# Chua_circuit.net
KiCad netlist of a schematic drawn in Altium Designer
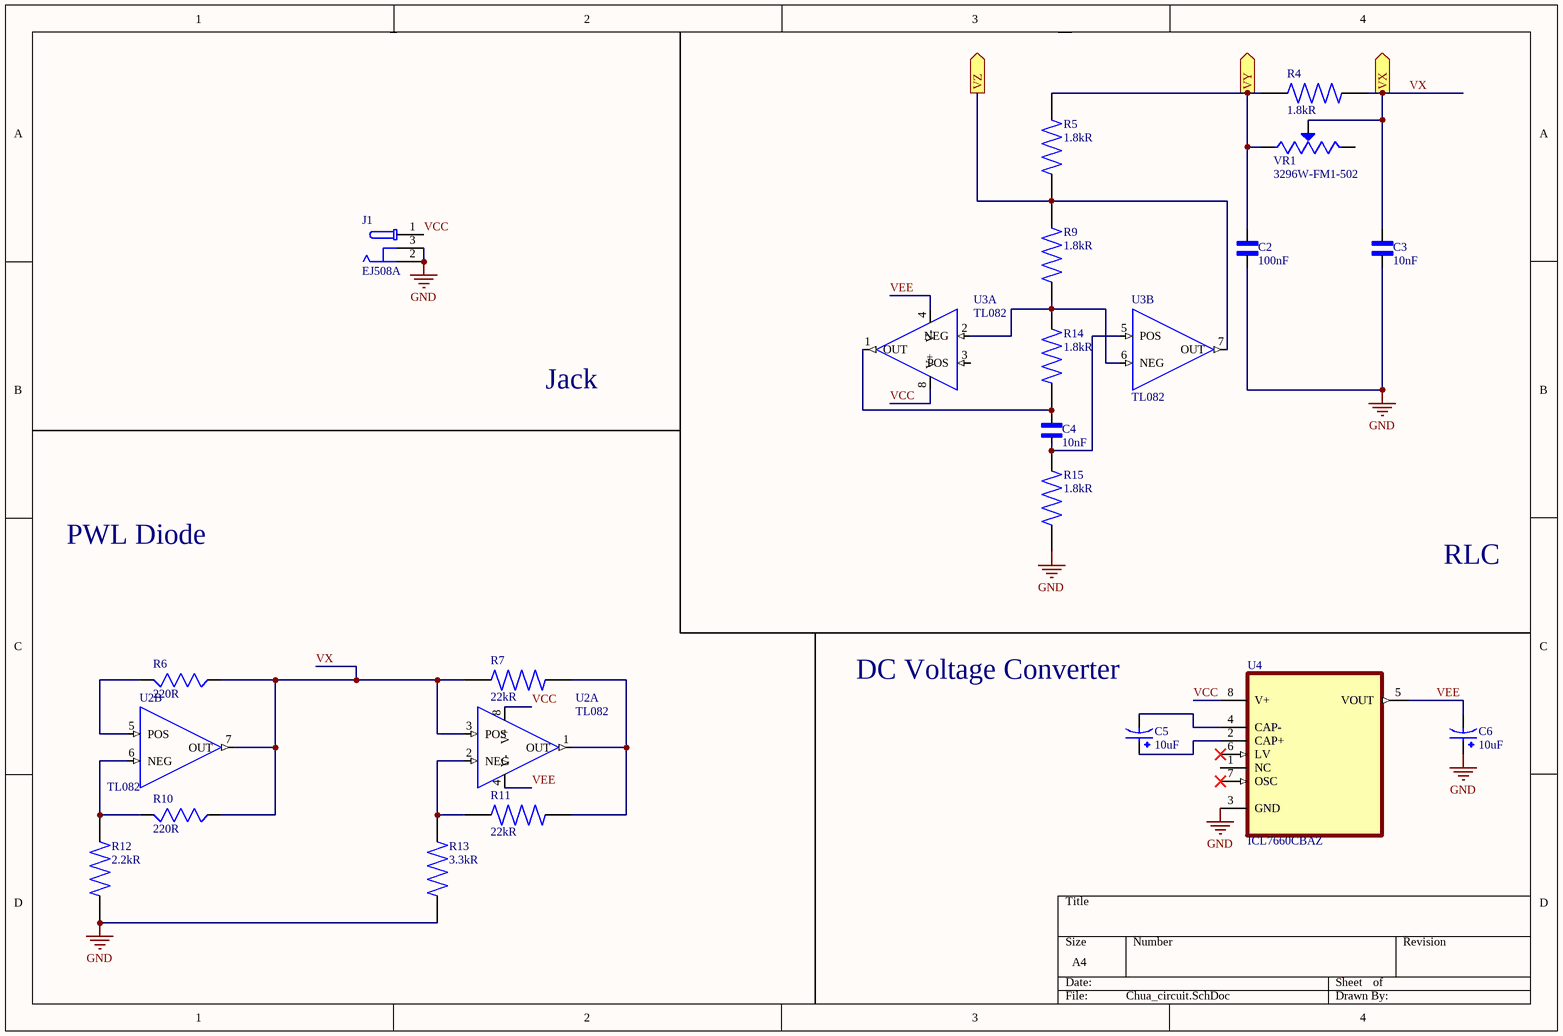
[diagram p0: Chua_circuit.SchDoc]

(export (version "E")
  (design (tool "Eeschema 10.0.6"))
  (components
    (comp (ref "C2")
      (value "100nF")
      (footprint "CAPC3216X100N")
      (description "Ceramic capacitor SMD 1206 100 nF 50 V 10 % Samsung Electro-Mechanics CL31B104KBCNNNC 4000 pc(s)")
      (fields (field (name "MF") "Samsung Electro-Mechanics") (field (name "MP") "CL31B104KBCNNNC"))
      (libsource (lib "CL31B104KBCNNNC") (part "CL31B104KBCNNNC"))
    )
    (comp (ref "C3")
      (value "10nF")
      (footprint "CAPC1608X90N")
      (description "0603 X7R ceramic capacitor,10nF 25V ¦ AVX 06033C103KAT2A")
      (fields (field (name "MF") "AVX") (field (name "MP") "06033C103KAT2A"))
      (libsource (lib "06033C103KAT2A") (part "06033C103KAT2A"))
    )
    (comp (ref "C4")
      (value "10nF")
      (footprint "CAPC1608X90N")
      (description "0603 X7R ceramic capacitor,10nF 25V ¦ AVX 06033C103KAT2A")
      (fields (field (name "MF") "AVX") (field (name "MP") "06033C103KAT2A"))
      (libsource (lib "06033C103KAT2A") (part "06033C103KAT2A"))
    )
    (comp (ref "C5")
      (value "10uF")
      (footprint "CAP_EEEFN1J100L")
      (description "CAP ALUM 10UF 20% 63V SMD")
      (fields (field (name "MF") "Panasonic") (field (name "MP") "EEEFN1J100L"))
      (libsource (lib "EEEFN1J100L") (part "EEEFN1J100L"))
    )
    (comp (ref "C6")
      (value "10uF")
      (footprint "CAP_EEEFN1J100L")
      (description "CAP ALUM 10UF 20% 63V SMD")
      (fields (field (name "MF") "Panasonic") (field (name "MP") "EEEFN1J100L"))
      (libsource (lib "EEEFN1J100L") (part "EEEFN1J100L"))
    )
    (comp (ref "J1")
      (value "EJ508A")
      (footprint "MPD_EJ508A")
      (description "Power Barrel Connector Jack 2.10mm ID _0.083_, 5.50mm OD _0.217_ Through Hole, Right Angle")
      (fields (field (name "MF") "MPD"))
      (libsource (lib "EJ508A") (part "EJ508A"))
    )
    (comp (ref "R4")
      (value "1.8kR")
      (footprint "RES_ERJU08F1801V")
      (fields (field (name "MP") "ERJU08F1801V"))
      (libsource (lib "ERJU08F1801V") (part "ERJU08F1801V"))
    )
    (comp (ref "R5")
      (value "1.8kR")
      (footprint "RES_ERJU08F1801V")
      (fields (field (name "MP") "ERJU08F1801V"))
      (libsource (lib "ERJU08F1801V") (part "ERJU08F1801V"))
    )
    (comp (ref "R6")
      (value "220R")
      (footprint "RESC2012X60N")
      (description "220 kOhms Â±1% 0.125W, 1/8W Chip Resistor 0805 (2012 Metric) - Thick Film")
      (fields (field (name "MP") "RC0805FR-10220KL") (field (name "MF") "Yageo"))
      (libsource (lib "RC0805FR-10220KL") (part "RC0805FR-10220KL"))
    )
    (comp (ref "R7")
      (value "22kR")
      (footprint "RES_ERA3AED223V")
      (fields (field (name "MP") "ERA3AED223V"))
      (libsource (lib "ERA3AED223V") (part "ERA3AED223V"))
    )
    (comp (ref "R9")
      (value "1.8kR")
      (footprint "RES_ERJU08F1801V")
      (fields (field (name "MP") "ERJU08F1801V"))
      (libsource (lib "ERJU08F1801V") (part "ERJU08F1801V"))
    )
    (comp (ref "R10")
      (value "220R")
      (footprint "RESC2012X60N")
      (description "220 kOhms Â±1% 0.125W, 1/8W Chip Resistor 0805 (2012 Metric) - Thick Film")
      (fields (field (name "MP") "RC0805FR-10220KL") (field (name "MF") "Yageo"))
      (libsource (lib "RC0805FR-10220KL") (part "RC0805FR-10220KL"))
    )
    (comp (ref "R11")
      (value "22kR")
      (footprint "RES_ERA3AED223V")
      (fields (field (name "MP") "ERA3AED223V"))
      (libsource (lib "ERA3AED223V") (part "ERA3AED223V"))
    )
    (comp (ref "R12")
      (value "2.2kR")
      (footprint "RESC1608X55N")
      (description "Res 0603 2k2 5% 100mW ¦ Bourns CR0603-JW-222ELF")
      (fields (field (name "MF") "Bourns") (field (name "MP") "CR0603-JW-222ELF"))
      (libsource (lib "CR0603-JW-222ELF") (part "CR0603-JW-222ELF"))
    )
    (comp (ref "R13")
      (value "3.3kR")
      (footprint "RESC1608X55N")
      (description "CR0603 SMD Thick Film Resistor,3K3 1% ¦ Bourns CR0603-FX-3301ELF")
      (fields (field (name "MF") "Bourns") (field (name "MP") "CR0603-FX-3301ELF"))
      (libsource (lib "CR0603-FX-3301ELF") (part "CR0603-FX-3301ELF"))
    )
    (comp (ref "R14")
      (value "1.8kR")
      (footprint "RES_ERJU08F1801V")
      (fields (field (name "MP") "ERJU08F1801V"))
      (libsource (lib "ERJU08F1801V") (part "ERJU08F1801V"))
    )
    (comp (ref "R15")
      (value "1.8kR")
      (footprint "RES_ERJU08F1801V")
      (fields (field (name "MP") "ERJU08F1801V"))
      (libsource (lib "ERJU08F1801V") (part "ERJU08F1801V"))
    )
    (comp (ref "U2")
      (value "TL082")
      (footprint "SOIC127P600X175-8N")
      (description "GENERAL PURPOSE J-FET DUAL OPERATIONAL AMPLIFIERS")
      (fields (field (name "MF") "STMicroelectronics"))
      (libsource (lib "TL082") (part "TL082"))
    )
    (comp (ref "U3")
      (value "TL082")
      (footprint "SOIC127P600X175-8N")
      (description "GENERAL PURPOSE J-FET DUAL OPERATIONAL AMPLIFIERS")
      (fields (field (name "MF") "STMicroelectronics"))
      (libsource (lib "TL082") (part "TL082"))
    )
    (comp (ref "U4")
      (value "ICL7660CBAZ")
      (footprint "SOIC127P600X175-8N")
      (fields (field (name "MF") "Renesas Electronics America Inc"))
      (libsource (lib "ICL7660CBAZ") (part "ICL7660CBAZ"))
    )
    (comp (ref "VR1")
      (value "3296W-FM1-502")
      (footprint "TRIM_3296W-FM1-502")
      (description "Trimmer Resistors - Through Hole")
      (fields (field (name "MF") "Bourns"))
      (libsource (lib "3296W-FM1-502") (part "3296W-FM1-502"))
    )
  )
  (nets
    (net (code "1") (name "/VCC") (class "Default")
      (node (ref "J1") (pin "1") (pinfunction "1_1") (pintype "passive"))
      (node (ref "U2") (pin "8") (pinfunction "V+_8") (pintype "power_in"))
      (node (ref "U3") (pin "8") (pinfunction "V+_8") (pintype "power_in"))
      (node (ref "U4") (pin "8") (pinfunction "V+_8") (pintype "power_in"))
    )
    (net (code "2") (name "/VEE") (class "Default")
      (node (ref "C6") (pin "2") (pinfunction "2_2") (pintype "passive"))
      (node (ref "U2") (pin "4") (pinfunction "V-_4") (pintype "power_in"))
      (node (ref "U3") (pin "4") (pinfunction "V-_4") (pintype "power_in"))
      (node (ref "U4") (pin "5") (pinfunction "VOUT_5") (pintype "output"))
    )
    (net (code "3") (name "/VX") (class "Default")
      (node (ref "C3") (pin "2") (pinfunction "2_2") (pintype "passive"))
      (node (ref "R10") (pin "2") (pinfunction "2_2") (pintype "passive"))
      (node (ref "R4") (pin "2") (pinfunction "2_2") (pintype "passive"))
      (node (ref "R6") (pin "2") (pinfunction "2_2") (pintype "passive"))
      (node (ref "R7") (pin "1") (pinfunction "1_1") (pintype "passive"))
      (node (ref "U2") (pin "3") (pinfunction "POS_3") (pintype "input"))
      (node (ref "U2") (pin "7") (pinfunction "OUT_7") (pintype "output"))
      (node (ref "VR1") (pin "2") (pinfunction "WIPER_2") (pintype "passive"))
    )
    (net (code "4") (name "/VY") (class "Default")
      (node (ref "C2") (pin "2") (pinfunction "2_2") (pintype "passive"))
      (node (ref "R4") (pin "1") (pinfunction "1_1") (pintype "passive"))
      (node (ref "R5") (pin "2") (pinfunction "2_2") (pintype "passive"))
      (node (ref "VR1") (pin "1") (pinfunction "CCW_1") (pintype "passive"))
    )
    (net (code "5") (name "/VZ") (class "Default")
      (node (ref "R5") (pin "1") (pinfunction "1_1") (pintype "passive"))
      (node (ref "R9") (pin "2") (pinfunction "2_2") (pintype "passive"))
      (node (ref "U3") (pin "7") (pinfunction "OUT_7") (pintype "output"))
    )
    (net (code "6") (name "GND") (class "Default")
      (node (ref "C2") (pin "1") (pinfunction "1_1") (pintype "passive"))
      (node (ref "C3") (pin "1") (pinfunction "1_1") (pintype "passive"))
      (node (ref "C6") (pin "1") (pinfunction "1_1") (pintype "passive"))
      (node (ref "J1") (pin "2") (pinfunction "2_2") (pintype "passive"))
      (node (ref "J1") (pin "3") (pinfunction "3_3") (pintype "passive"))
      (node (ref "R12") (pin "2") (pinfunction "2_2") (pintype "passive"))
      (node (ref "R13") (pin "1") (pinfunction "1_1") (pintype "passive"))
      (node (ref "R15") (pin "1") (pinfunction "1_1") (pintype "passive"))
      (node (ref "U4") (pin "3") (pinfunction "GND_3") (pintype "passive"))
    )
    (net (code "7") (name "Net-(U2A-NEG)") (class "Default")
      (node (ref "R11") (pin "1") (pinfunction "1_1") (pintype "passive"))
      (node (ref "R13") (pin "2") (pinfunction "2_2") (pintype "passive"))
      (node (ref "U2") (pin "2") (pinfunction "NEG_2") (pintype "input"))
    )
    (net (code "8") (name "Net-(U2A-OUT)") (class "Default")
      (node (ref "R11") (pin "2") (pinfunction "2_2") (pintype "passive"))
      (node (ref "R7") (pin "2") (pinfunction "2_2") (pintype "passive"))
      (node (ref "U2") (pin "1") (pinfunction "OUT_1") (pintype "output"))
    )
    (net (code "9") (name "Net-(U2B-NEG)") (class "Default")
      (node (ref "R10") (pin "1") (pinfunction "1_1") (pintype "passive"))
      (node (ref "R12") (pin "1") (pinfunction "1_1") (pintype "passive"))
      (node (ref "U2") (pin "6") (pinfunction "NEG_6") (pintype "input"))
    )
    (net (code "10") (name "Net-(U2B-POS)") (class "Default")
      (node (ref "R6") (pin "1") (pinfunction "1_1") (pintype "passive"))
      (node (ref "U2") (pin "5") (pinfunction "POS_5") (pintype "input"))
    )
    (net (code "11") (name "Net-(U3A-NEG)") (class "Default")
      (node (ref "R14") (pin "2") (pinfunction "2_2") (pintype "passive"))
      (node (ref "R9") (pin "1") (pinfunction "1_1") (pintype "passive"))
      (node (ref "U3") (pin "2") (pinfunction "NEG_2") (pintype "input"))
      (node (ref "U3") (pin "6") (pinfunction "NEG_6") (pintype "input"))
    )
    (net (code "12") (name "Net-(U3A-OUT)") (class "Default")
      (node (ref "C4") (pin "2") (pinfunction "2_2") (pintype "passive"))
      (node (ref "R14") (pin "1") (pinfunction "1_1") (pintype "passive"))
      (node (ref "U3") (pin "1") (pinfunction "OUT_1") (pintype "output"))
    )
    (net (code "13") (name "Net-(U3B-POS)") (class "Default")
      (node (ref "C4") (pin "1") (pinfunction "1_1") (pintype "passive"))
      (node (ref "R15") (pin "2") (pinfunction "2_2") (pintype "passive"))
      (node (ref "U3") (pin "5") (pinfunction "POS_5") (pintype "input"))
    )
    (net (code "14") (name "Net-(U4-CAP+)") (class "Default")
      (node (ref "C5") (pin "1") (pinfunction "1_1") (pintype "passive"))
      (node (ref "U4") (pin "2") (pinfunction "CAP+_2") (pintype "passive"))
    )
    (net (code "15") (name "Net-(U4-CAP-)") (class "Default")
      (node (ref "C5") (pin "2") (pinfunction "2_2") (pintype "passive"))
      (node (ref "U4") (pin "4") (pinfunction "CAP-_4") (pintype "passive"))
    )
    (net (code "16") (name "unconnected-(U3A-POS-Pad3)") (class "Default")
      (node (ref "U3") (pin "3") (pinfunction "POS_3") (pintype "input"))
    )
    (net (code "17") (name "unconnected-(U4-LV-Pad6)") (class "Default")
      (node (ref "U4") (pin "6") (pinfunction "LV_6") (pintype "input+no_connect"))
    )
    (net (code "18") (name "unconnected-(U4-NC-Pad1)") (class "Default")
      (node (ref "U4") (pin "1") (pinfunction "NC_1") (pintype "passive"))
    )
    (net (code "19") (name "unconnected-(U4-OSC-Pad7)") (class "Default")
      (node (ref "U4") (pin "7") (pinfunction "OSC_7") (pintype "input+no_connect"))
    )
    (net (code "20") (name "unconnected-(VR1-CW-Pad3)") (class "Default")
      (node (ref "VR1") (pin "3") (pinfunction "CW_3") (pintype "passive"))
    )
  )
)
